# 4th_4G_-_V4_1.net
KiCad netlist of a schematic drawn in Altium Designer
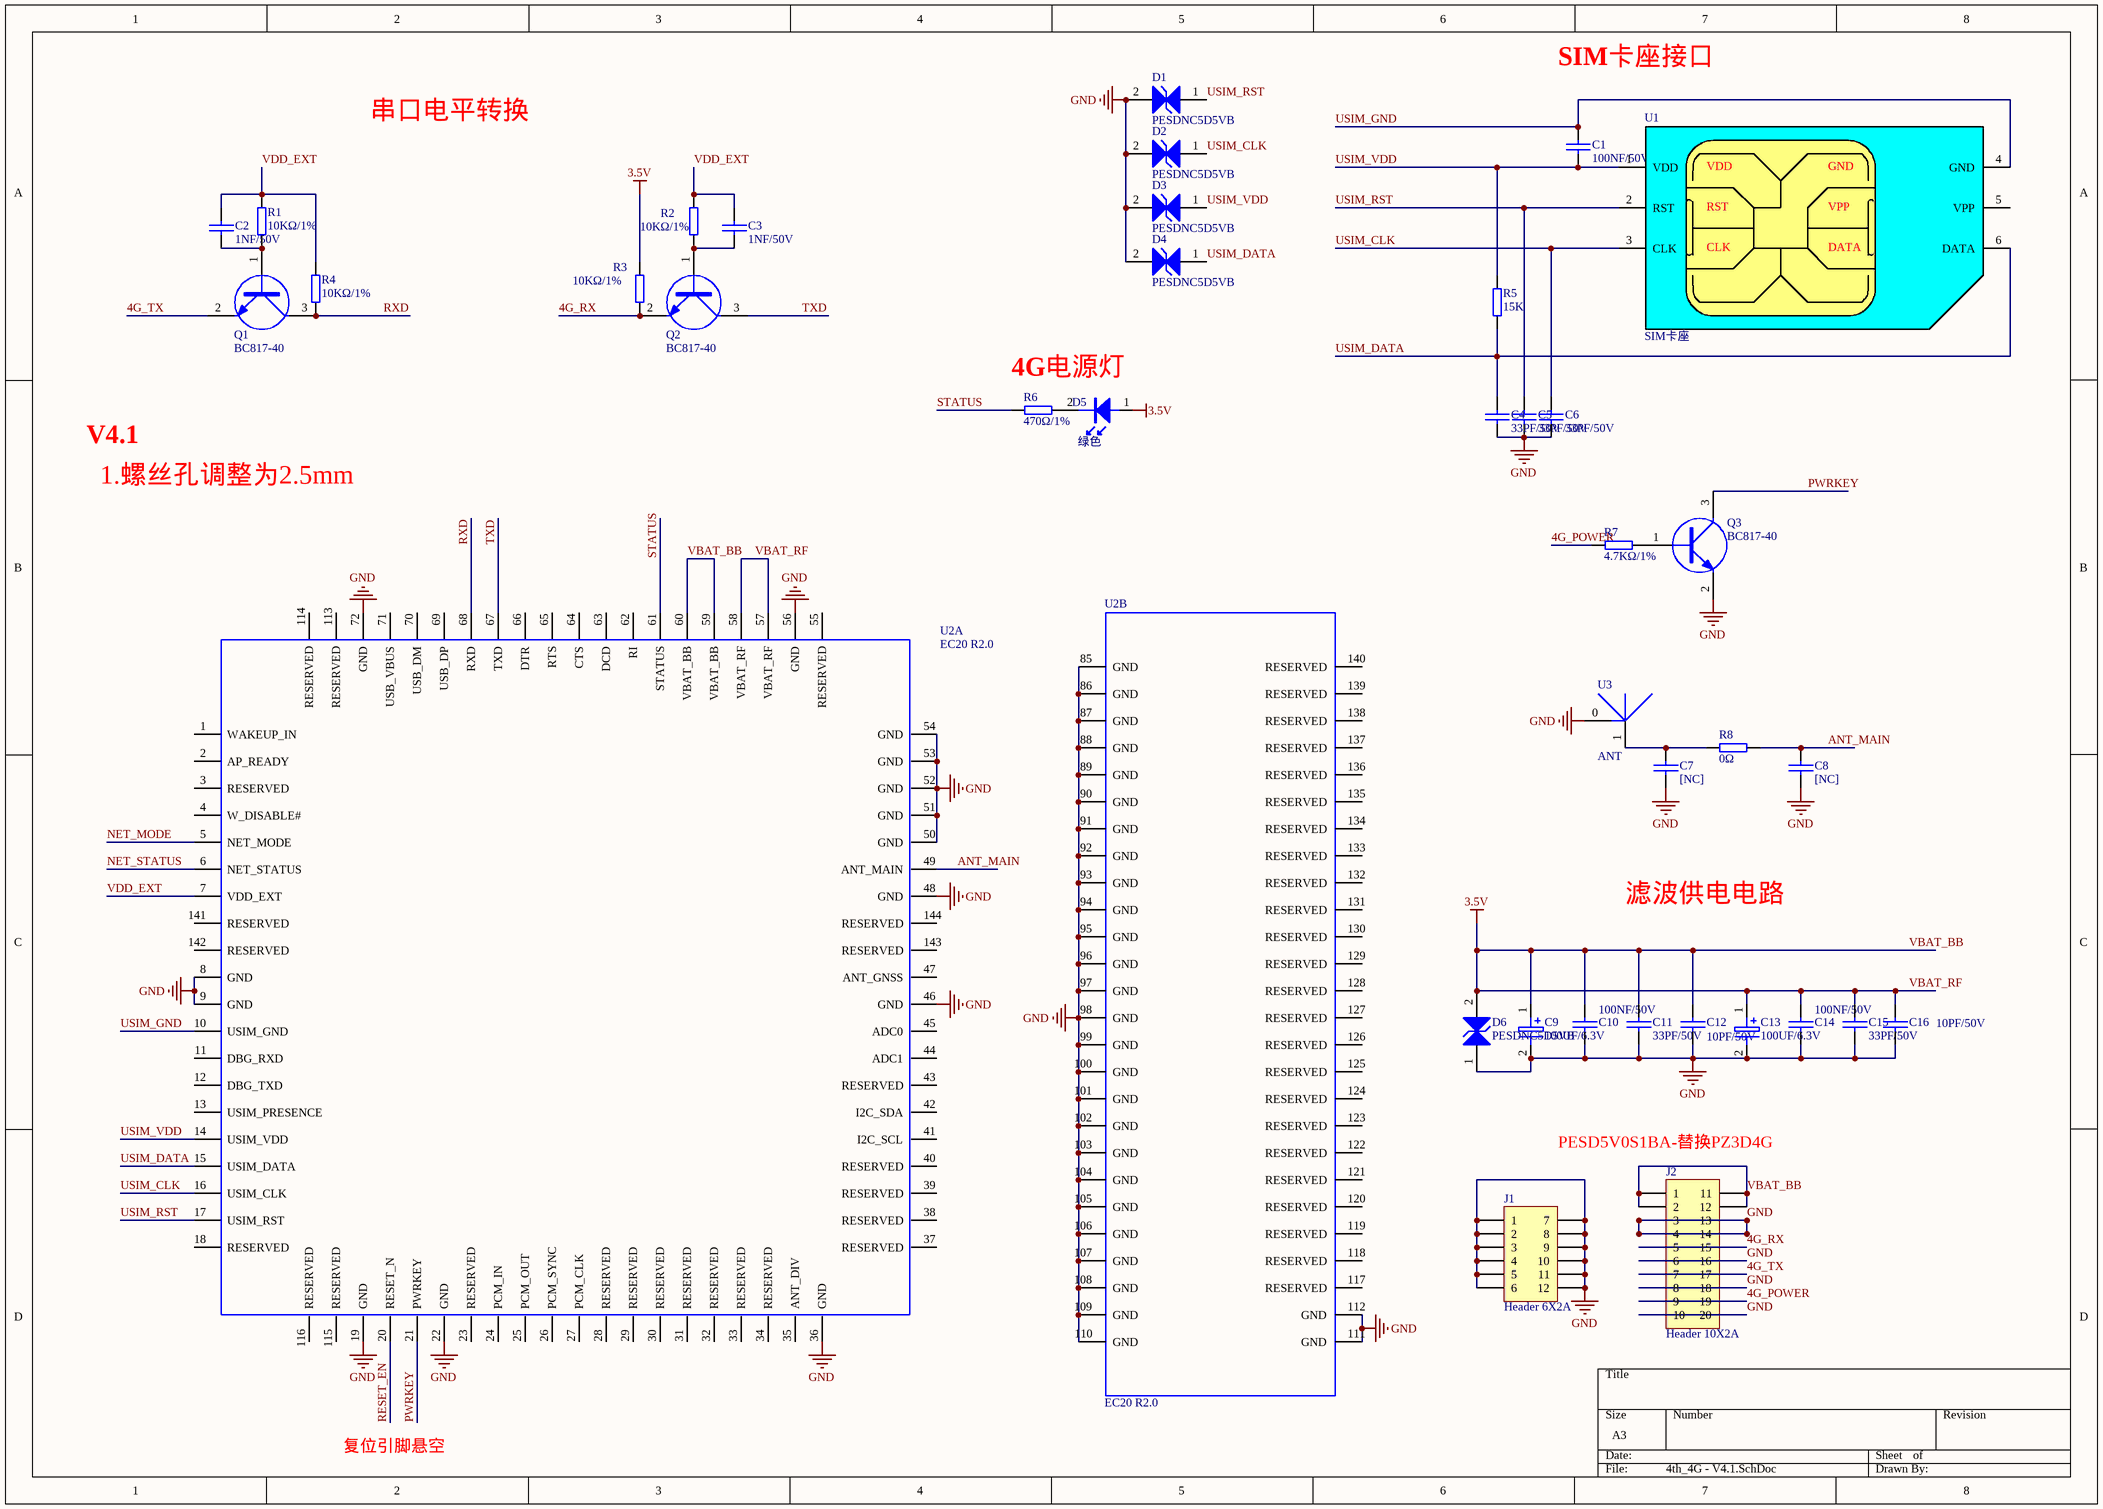
[diagram p0: 4th_4G - V4.1.SchDoc]

(export (version "E")
  (design (tool "Eeschema 10.0.6"))
  (components
    (comp (ref "C1")
      (value "100NF/50V")
      (footprint "0603_C")
      (description "无极性电容")
      (libsource (lib "Integrated_Library") (part "CAP"))
    )
    (comp (ref "C2")
      (value "1NF/50V")
      (footprint "0603_C")
      (description "无极性电容")
      (libsource (lib "Integrated_Library") (part "CAP"))
    )
    (comp (ref "C3")
      (value "1NF/50V")
      (footprint "0603_C")
      (description "无极性电容")
      (libsource (lib "Integrated_Library") (part "CAP"))
    )
    (comp (ref "C4")
      (value "33PF/50V")
      (footprint "0603_C")
      (description "无极性电容")
      (libsource (lib "Integrated_Library") (part "CAP"))
    )
    (comp (ref "C5")
      (value "33PF/50V")
      (footprint "0603_C")
      (description "无极性电容")
      (libsource (lib "Integrated_Library") (part "CAP"))
    )
    (comp (ref "C6")
      (value "33PF/50V")
      (footprint "0603_C")
      (description "无极性电容")
      (libsource (lib "Integrated_Library") (part "CAP"))
    )
    (comp (ref "C7")
      (value "[NC]")
      (footprint "0603_C")
      (description "无极性电容")
      (libsource (lib "Integrated_Library") (part "CAP"))
    )
    (comp (ref "C8")
      (value "[NC]")
      (footprint "0603_C")
      (description "无极性电容")
      (libsource (lib "Integrated_Library") (part "CAP"))
    )
    (comp (ref "C9")
      (value "100UF/6.3V")
      (footprint "CASE-B_3528")
      (description "钽电容")
      (libsource (lib "Integrated_Library") (part "CAP POLAR"))
    )
    (comp (ref "C10")
      (value "100NF/50V")
      (footprint "0603_C")
      (description "无极性电容")
      (libsource (lib "Integrated_Library") (part "CAP"))
    )
    (comp (ref "C11")
      (value "33PF/50V")
      (footprint "0603_C")
      (description "无极性电容")
      (libsource (lib "Integrated_Library") (part "CAP"))
    )
    (comp (ref "C12")
      (value "10PF/50V")
      (footprint "0603_C")
      (description "无极性电容")
      (libsource (lib "Integrated_Library") (part "CAP"))
    )
    (comp (ref "C13")
      (value "100UF/6.3V")
      (footprint "CASE-B_3528")
      (description "钽电容")
      (libsource (lib "Integrated_Library") (part "CAP POLAR"))
    )
    (comp (ref "C14")
      (value "100NF/50V")
      (footprint "0603_C")
      (description "无极性电容")
      (libsource (lib "Integrated_Library") (part "CAP"))
    )
    (comp (ref "C15")
      (value "33PF/50V")
      (footprint "0603_C")
      (description "无极性电容")
      (libsource (lib "Integrated_Library") (part "CAP"))
    )
    (comp (ref "C16")
      (value "10PF/50V")
      (footprint "0603_C")
      (description "无极性电容")
      (libsource (lib "Integrated_Library") (part "CAP"))
    )
    (comp (ref "D1")
      (value "PESDNC5D5VB")
      (footprint "SOD-523")
      (description "TVS 瞬态抑制二极管")
      (fields (field (name "PUBLISHER") "Altium Limited"))
      (libsource (lib "Integrated_Library") (part "TVS"))
    )
    (comp (ref "D2")
      (value "PESDNC5D5VB")
      (footprint "SOD-523")
      (description "TVS 瞬态抑制二极管")
      (fields (field (name "PUBLISHER") "Altium Limited"))
      (libsource (lib "Integrated_Library") (part "TVS"))
    )
    (comp (ref "D3")
      (value "PESDNC5D5VB")
      (footprint "SOD-523")
      (description "TVS 瞬态抑制二极管")
      (fields (field (name "PUBLISHER") "Altium Limited"))
      (libsource (lib "Integrated_Library") (part "TVS"))
    )
    (comp (ref "D4")
      (value "PESDNC5D5VB")
      (footprint "SOD-523")
      (description "TVS 瞬态抑制二极管")
      (fields (field (name "PUBLISHER") "Altium Limited"))
      (libsource (lib "Integrated_Library") (part "TVS"))
    )
    (comp (ref "D5")
      (value "绿色")
      (footprint "0603_D")
      (description "发光二极管")
      (libsource (lib "Integrated_Library") (part "LED"))
    )
    (comp (ref "D6")
      (value "PESDNC5D5VB")
      (footprint "SOD-523")
      (description "TVS 瞬态抑制二极管")
      (fields (field (name "PUBLISHER") "Altium Limited"))
      (libsource (lib "Integrated_Library") (part "TVS"))
    )
    (comp (ref "J1")
      (value "Header 6X2A")
      (footprint "HDR2X6_CEN")
      (description "Header, 6-Pin, Dual row")
      (fields (field (name "PUBLISHER") "Altium Limited"))
      (libsource (lib "Miscellaneous Connectors") (part "Header 6X2A"))
    )
    (comp (ref "J2")
      (value "Header 10X2A")
      (footprint "HDR2X10_CEN")
      (description "Header, 10-Pin, Dual row")
      (fields (field (name "PUBLISHER") "Altium Limited"))
      (libsource (lib "Miscellaneous Connectors") (part "Header 10X2A"))
    )
    (comp (ref "Q1")
      (value "BC817-40")
      (footprint "SOT-23-3")
      (description "NPN")
      (libsource (lib "Integrated_Library") (part "S8050"))
    )
    (comp (ref "Q2")
      (value "BC817-40")
      (footprint "SOT-23-3")
      (description "NPN")
      (libsource (lib "Integrated_Library") (part "S8050"))
    )
    (comp (ref "Q3")
      (value "BC817-40")
      (footprint "SOT-23-3")
      (description "NPN三极管")
      (libsource (lib "Integrated_Library") (part "BC817-40"))
    )
    (comp (ref "R1")
      (value "10KΩ/1%")
      (footprint "0603_R")
      (description "电阻")
      (libsource (lib "Integrated_Library") (part "RES2"))
    )
    (comp (ref "R2")
      (value "10KΩ/1%")
      (footprint "0603_R")
      (description "电阻")
      (libsource (lib "Integrated_Library") (part "RES2"))
    )
    (comp (ref "R3")
      (value "10KΩ/1%")
      (footprint "0603_R")
      (description "电阻")
      (libsource (lib "Integrated_Library") (part "RES2"))
    )
    (comp (ref "R4")
      (value "10KΩ/1%")
      (footprint "0603_R")
      (description "电阻")
      (libsource (lib "Integrated_Library") (part "RES2"))
    )
    (comp (ref "R5")
      (value "15K")
      (footprint "0603_R")
      (description "电阻")
      (libsource (lib "Integrated_Library") (part "RES2"))
    )
    (comp (ref "R6")
      (value "470Ω/1%")
      (footprint "0603_R")
      (description "电阻")
      (libsource (lib "Integrated_Library") (part "RES2"))
    )
    (comp (ref "R7")
      (value "4.7KΩ/1%")
      (footprint "0603_R")
      (description "电阻")
      (libsource (lib "Integrated_Library") (part "RES2"))
    )
    (comp (ref "R8")
      (value "0Ω")
      (footprint "0603_R")
      (description "电阻")
      (libsource (lib "Integrated_Library") (part "RES2"))
    )
    (comp (ref "U1")
      (value "SIM卡座")
      (footprint "SIM卡座-NANO掀盖式")
      (description "无保护引脚SIM卡座")
      (libsource (lib "MyLib Schlib") (part "SIM卡座"))
    )
    (comp (ref "U2")
      (value "EC20 R2.0")
      (footprint "EC20_R2.0")
      (description "移远通信4G")
      (libsource (lib "Integrated_Library") (part "EC20 R2.0"))
    )
    (comp (ref "U3")
      (value "ANT")
      (footprint "SMA-KWE/弯头")
      (description "天线座")
      (libsource (lib "Integrated_Library") (part "ANT"))
    )
  )
  (nets
    (net (code "1") (name "/4G_POWER") (class "Default")
      (node (ref "J2") (pin "19") (pinfunction "19_19") (pintype "passive"))
      (node (ref "J2") (pin "9") (pinfunction "9_9") (pintype "passive"))
      (node (ref "R7") (pin "1") (pinfunction "1_1") (pintype "passive"))
    )
    (net (code "2") (name "/4G_RX") (class "Default")
      (node (ref "J2") (pin "15") (pinfunction "15_15") (pintype "passive"))
      (node (ref "J2") (pin "5") (pinfunction "5_5") (pintype "passive"))
      (node (ref "Q2") (pin "2") (pinfunction "2_2") (pintype "passive"))
      (node (ref "R3") (pin "1") (pinfunction "1_1") (pintype "passive"))
    )
    (net (code "3") (name "/4G_TX") (class "Default")
      (node (ref "J2") (pin "17") (pinfunction "17_17") (pintype "passive"))
      (node (ref "J2") (pin "7") (pinfunction "7_7") (pintype "passive"))
      (node (ref "Q1") (pin "2") (pinfunction "2_2") (pintype "passive"))
    )
    (net (code "4") (name "/ANT_MAIN") (class "Default")
      (node (ref "C8") (pin "1") (pinfunction "1_1") (pintype "passive"))
      (node (ref "R8") (pin "2") (pinfunction "2_2") (pintype "passive"))
      (node (ref "U2") (pin "49") (pinfunction "ANT_MAIN_49") (pintype "passive"))
    )
    (net (code "5") (name "/NET_MODE") (class "Default")
      (node (ref "U2") (pin "5") (pinfunction "NET_MODE_5") (pintype "passive"))
    )
    (net (code "6") (name "/NET_STATUS") (class "Default")
      (node (ref "U2") (pin "6") (pinfunction "NET_STATUS_6") (pintype "passive"))
    )
    (net (code "7") (name "/PWRKEY") (class "Default")
      (node (ref "Q3") (pin "3") (pinfunction "3_3") (pintype "passive"))
      (node (ref "U2") (pin "21") (pinfunction "PWRKEY_21") (pintype "passive"))
    )
    (net (code "8") (name "/RESET_EN") (class "Default")
      (node (ref "U2") (pin "20") (pinfunction "RESET_N_20") (pintype "passive"))
    )
    (net (code "9") (name "/RXD") (class "Default")
      (node (ref "Q1") (pin "3") (pinfunction "3_3") (pintype "passive"))
      (node (ref "R4") (pin "1") (pinfunction "1_1") (pintype "passive"))
      (node (ref "U2") (pin "68") (pinfunction "RXD_68") (pintype "passive"))
    )
    (net (code "10") (name "/STATUS") (class "Default")
      (node (ref "R6") (pin "1") (pinfunction "1_1") (pintype "passive"))
      (node (ref "U2") (pin "61") (pinfunction "STATUS_61") (pintype "passive"))
    )
    (net (code "11") (name "/TXD") (class "Default")
      (node (ref "Q2") (pin "3") (pinfunction "3_3") (pintype "passive"))
      (node (ref "U2") (pin "67") (pinfunction "TXD_67") (pintype "passive"))
    )
    (net (code "12") (name "/USIM_CLK") (class "Default")
      (node (ref "C6") (pin "1") (pinfunction "1_1") (pintype "passive"))
      (node (ref "D2") (pin "1") (pinfunction "1_1") (pintype "passive"))
      (node (ref "U1") (pin "3") (pinfunction "CLK_3") (pintype "passive"))
      (node (ref "U2") (pin "16") (pinfunction "USIM_CLK_16") (pintype "passive"))
    )
    (net (code "13") (name "/USIM_DATA") (class "Default")
      (node (ref "C4") (pin "1") (pinfunction "1_1") (pintype "passive"))
      (node (ref "D4") (pin "1") (pinfunction "1_1") (pintype "passive"))
      (node (ref "R5") (pin "1") (pinfunction "1_1") (pintype "passive"))
      (node (ref "U1") (pin "6") (pinfunction "DATA_6") (pintype "passive"))
      (node (ref "U2") (pin "15") (pinfunction "USIM_DATA_15") (pintype "passive"))
    )
    (net (code "14") (name "/USIM_GND") (class "Default")
      (node (ref "C1") (pin "1") (pinfunction "1_1") (pintype "passive"))
      (node (ref "U1") (pin "4") (pinfunction "GND_4") (pintype "passive"))
      (node (ref "U2") (pin "10") (pinfunction "USIM_GND_10") (pintype "passive"))
    )
    (net (code "15") (name "/USIM_RST") (class "Default")
      (node (ref "C5") (pin "1") (pinfunction "1_1") (pintype "passive"))
      (node (ref "D1") (pin "1") (pinfunction "1_1") (pintype "passive"))
      (node (ref "U1") (pin "2") (pinfunction "RST_2") (pintype "passive"))
      (node (ref "U2") (pin "17") (pinfunction "USIM_RST_17") (pintype "passive"))
    )
    (net (code "16") (name "/USIM_VDD") (class "Default")
      (node (ref "C1") (pin "2") (pinfunction "2_2") (pintype "passive"))
      (node (ref "D3") (pin "1") (pinfunction "1_1") (pintype "passive"))
      (node (ref "R5") (pin "2") (pinfunction "2_2") (pintype "passive"))
      (node (ref "U1") (pin "1") (pinfunction "VDD_1") (pintype "passive"))
      (node (ref "U2") (pin "14") (pinfunction "USIM_VDD_14") (pintype "passive"))
    )
    (net (code "17") (name "/VDD_EXT") (class "Default")
      (node (ref "C2") (pin "1") (pinfunction "1_1") (pintype "passive"))
      (node (ref "C3") (pin "1") (pinfunction "1_1") (pintype "passive"))
      (node (ref "R1") (pin "2") (pinfunction "2_2") (pintype "passive"))
      (node (ref "R2") (pin "2") (pinfunction "2_2") (pintype "passive"))
      (node (ref "R4") (pin "2") (pinfunction "2_2") (pintype "passive"))
      (node (ref "U2") (pin "7") (pinfunction "VDD_EXT_7") (pintype "passive"))
    )
    (net (code "18") (name "3.5V") (class "Default")
      (node (ref "C10") (pin "1") (pinfunction "1_1") (pintype "passive"))
      (node (ref "C11") (pin "1") (pinfunction "1_1") (pintype "passive"))
      (node (ref "C12") (pin "1") (pinfunction "1_1") (pintype "passive"))
      (node (ref "C13") (pin "1") (pinfunction "1_1") (pintype "passive"))
      (node (ref "C14") (pin "1") (pinfunction "1_1") (pintype "passive"))
      (node (ref "C15") (pin "1") (pinfunction "1_1") (pintype "passive"))
      (node (ref "C16") (pin "1") (pinfunction "1_1") (pintype "passive"))
      (node (ref "C9") (pin "1") (pinfunction "1_1") (pintype "passive"))
      (node (ref "D5") (pin "1") (pinfunction "1_1") (pintype "passive"))
      (node (ref "D6") (pin "2") (pinfunction "K_2") (pintype "passive"))
      (node (ref "J2") (pin "1") (pinfunction "1_1") (pintype "passive"))
      (node (ref "J2") (pin "11") (pinfunction "11_11") (pintype "passive"))
      (node (ref "J2") (pin "12") (pinfunction "12_12") (pintype "passive"))
      (node (ref "J2") (pin "2") (pinfunction "2_2") (pintype "passive"))
      (node (ref "R3") (pin "2") (pinfunction "2_2") (pintype "passive"))
      (node (ref "U2") (pin "57") (pinfunction "VBAT_RF_57") (pintype "passive"))
      (node (ref "U2") (pin "58") (pinfunction "VBAT_RF_58") (pintype "passive"))
      (node (ref "U2") (pin "59") (pinfunction "VBAT_BB_59") (pintype "passive"))
      (node (ref "U2") (pin "60") (pinfunction "VBAT_BB_60") (pintype "passive"))
    )
    (net (code "19") (name "GND") (class "Default")
      (node (ref "C10") (pin "2") (pinfunction "2_2") (pintype "passive"))
      (node (ref "C11") (pin "2") (pinfunction "2_2") (pintype "passive"))
      (node (ref "C12") (pin "2") (pinfunction "2_2") (pintype "passive"))
      (node (ref "C13") (pin "2") (pinfunction "2_2") (pintype "passive"))
      (node (ref "C14") (pin "2") (pinfunction "2_2") (pintype "passive"))
      (node (ref "C15") (pin "2") (pinfunction "2_2") (pintype "passive"))
      (node (ref "C16") (pin "2") (pinfunction "2_2") (pintype "passive"))
      (node (ref "C4") (pin "2") (pinfunction "2_2") (pintype "passive"))
      (node (ref "C5") (pin "2") (pinfunction "2_2") (pintype "passive"))
      (node (ref "C6") (pin "2") (pinfunction "2_2") (pintype "passive"))
      (node (ref "C7") (pin "2") (pinfunction "2_2") (pintype "passive"))
      (node (ref "C8") (pin "2") (pinfunction "2_2") (pintype "passive"))
      (node (ref "C9") (pin "2") (pinfunction "2_2") (pintype "passive"))
      (node (ref "D1") (pin "2") (pinfunction "K_2") (pintype "passive"))
      (node (ref "D2") (pin "2") (pinfunction "K_2") (pintype "passive"))
      (node (ref "D3") (pin "2") (pinfunction "K_2") (pintype "passive"))
      (node (ref "D4") (pin "2") (pinfunction "K_2") (pintype "passive"))
      (node (ref "D6") (pin "1") (pinfunction "1_1") (pintype "passive"))
      (node (ref "J1") (pin "1") (pinfunction "1_1") (pintype "passive"))
      (node (ref "J1") (pin "10") (pinfunction "10_10") (pintype "passive"))
      (node (ref "J1") (pin "11") (pinfunction "11_11") (pintype "passive"))
      (node (ref "J1") (pin "12") (pinfunction "12_12") (pintype "passive"))
      (node (ref "J1") (pin "2") (pinfunction "2_2") (pintype "passive"))
      (node (ref "J1") (pin "3") (pinfunction "3_3") (pintype "passive"))
      (node (ref "J1") (pin "4") (pinfunction "4_4") (pintype "passive"))
      (node (ref "J1") (pin "5") (pinfunction "5_5") (pintype "passive"))
      (node (ref "J1") (pin "6") (pinfunction "6_6") (pintype "passive"))
      (node (ref "J1") (pin "7") (pinfunction "7_7") (pintype "passive"))
      (node (ref "J1") (pin "8") (pinfunction "8_8") (pintype "passive"))
      (node (ref "J1") (pin "9") (pinfunction "9_9") (pintype "passive"))
      (node (ref "J2") (pin "10") (pinfunction "10_10") (pintype "passive"))
      (node (ref "J2") (pin "13") (pinfunction "13_13") (pintype "passive"))
      (node (ref "J2") (pin "14") (pinfunction "14_14") (pintype "passive"))
      (node (ref "J2") (pin "16") (pinfunction "16_16") (pintype "passive"))
      (node (ref "J2") (pin "18") (pinfunction "18_18") (pintype "passive"))
      (node (ref "J2") (pin "20") (pinfunction "20_20") (pintype "passive"))
      (node (ref "J2") (pin "3") (pinfunction "3_3") (pintype "passive"))
      (node (ref "J2") (pin "4") (pinfunction "4_4") (pintype "passive"))
      (node (ref "J2") (pin "6") (pinfunction "6_6") (pintype "passive"))
      (node (ref "J2") (pin "8") (pinfunction "8_8") (pintype "passive"))
      (node (ref "Q3") (pin "2") (pinfunction "2_2") (pintype "passive"))
      (node (ref "U2") (pin "100") (pinfunction "GND_100") (pintype "passive"))
      (node (ref "U2") (pin "101") (pinfunction "GND_101") (pintype "passive"))
      (node (ref "U2") (pin "102") (pinfunction "GND_102") (pintype "passive"))
      (node (ref "U2") (pin "103") (pinfunction "GND_103") (pintype "passive"))
      (node (ref "U2") (pin "104") (pinfunction "GND_104") (pintype "passive"))
      (node (ref "U2") (pin "105") (pinfunction "GND_105") (pintype "passive"))
      (node (ref "U2") (pin "106") (pinfunction "GND_106") (pintype "passive"))
      (node (ref "U2") (pin "107") (pinfunction "GND_107") (pintype "passive"))
      (node (ref "U2") (pin "108") (pinfunction "GND_108") (pintype "passive"))
      (node (ref "U2") (pin "109") (pinfunction "GND_109") (pintype "passive"))
      (node (ref "U2") (pin "110") (pinfunction "GND_110") (pintype "passive"))
      (node (ref "U2") (pin "111") (pinfunction "GND_111") (pintype "passive"))
      (node (ref "U2") (pin "112") (pinfunction "GND_112") (pintype "passive"))
      (node (ref "U2") (pin "19") (pinfunction "GND_19") (pintype "passive"))
      (node (ref "U2") (pin "22") (pinfunction "GND_22") (pintype "passive"))
      (node (ref "U2") (pin "36") (pinfunction "GND_36") (pintype "passive"))
      (node (ref "U2") (pin "46") (pinfunction "GND_46") (pintype "passive"))
      (node (ref "U2") (pin "48") (pinfunction "GND_48") (pintype "passive"))
      (node (ref "U2") (pin "50") (pinfunction "GND_50") (pintype "passive"))
      (node (ref "U2") (pin "51") (pinfunction "GND_51") (pintype "passive"))
      (node (ref "U2") (pin "52") (pinfunction "GND_52") (pintype "passive"))
      (node (ref "U2") (pin "53") (pinfunction "GND_53") (pintype "passive"))
      (node (ref "U2") (pin "54") (pinfunction "GND_54") (pintype "passive"))
      (node (ref "U2") (pin "56") (pinfunction "GND_56") (pintype "passive"))
      (node (ref "U2") (pin "72") (pinfunction "GND_72") (pintype "passive"))
      (node (ref "U2") (pin "8") (pinfunction "GND_8") (pintype "passive"))
      (node (ref "U2") (pin "85") (pinfunction "GND_85") (pintype "passive"))
      (node (ref "U2") (pin "86") (pinfunction "GND_86") (pintype "passive"))
      (node (ref "U2") (pin "87") (pinfunction "GND_87") (pintype "passive"))
      (node (ref "U2") (pin "88") (pinfunction "GND_88") (pintype "passive"))
      (node (ref "U2") (pin "89") (pinfunction "GND_89") (pintype "passive"))
      (node (ref "U2") (pin "9") (pinfunction "GND_9") (pintype "passive"))
      (node (ref "U2") (pin "90") (pinfunction "GND_90") (pintype "passive"))
      (node (ref "U2") (pin "91") (pinfunction "GND_91") (pintype "passive"))
      (node (ref "U2") (pin "92") (pinfunction "GND_92") (pintype "passive"))
      (node (ref "U2") (pin "93") (pinfunction "GND_93") (pintype "passive"))
      (node (ref "U2") (pin "94") (pinfunction "GND_94") (pintype "passive"))
      (node (ref "U2") (pin "95") (pinfunction "GND_95") (pintype "passive"))
      (node (ref "U2") (pin "96") (pinfunction "GND_96") (pintype "passive"))
      (node (ref "U2") (pin "97") (pinfunction "GND_97") (pintype "passive"))
      (node (ref "U2") (pin "98") (pinfunction "GND_98") (pintype "passive"))
      (node (ref "U2") (pin "99") (pinfunction "GND_99") (pintype "passive"))
      (node (ref "U3") (pin "0") (pinfunction "0_0") (pintype "passive"))
    )
    (net (code "20") (name "Net-(C2-Pad2)") (class "Default")
      (node (ref "C2") (pin "2") (pinfunction "2_2") (pintype "passive"))
      (node (ref "Q1") (pin "1") (pinfunction "1_1") (pintype "passive"))
      (node (ref "R1") (pin "1") (pinfunction "1_1") (pintype "passive"))
    )
    (net (code "21") (name "Net-(C3-Pad2)") (class "Default")
      (node (ref "C3") (pin "2") (pinfunction "2_2") (pintype "passive"))
      (node (ref "Q2") (pin "1") (pinfunction "1_1") (pintype "passive"))
      (node (ref "R2") (pin "1") (pinfunction "1_1") (pintype "passive"))
    )
    (net (code "22") (name "Net-(C7-Pad1)") (class "Default")
      (node (ref "C7") (pin "1") (pinfunction "1_1") (pintype "passive"))
      (node (ref "R8") (pin "1") (pinfunction "1_1") (pintype "passive"))
      (node (ref "U3") (pin "1") (pinfunction "1_1") (pintype "passive"))
    )
    (net (code "23") (name "Net-(D5-Pad2)") (class "Default")
      (node (ref "D5") (pin "2") (pinfunction "2_2") (pintype "passive"))
      (node (ref "R6") (pin "2") (pinfunction "2_2") (pintype "passive"))
    )
    (net (code "24") (name "Net-(Q3-Pad1)") (class "Default")
      (node (ref "Q3") (pin "1") (pinfunction "1_1") (pintype "passive"))
      (node (ref "R7") (pin "2") (pinfunction "2_2") (pintype "passive"))
    )
    (net (code "25") (name "unconnected-(U1-VPP-Pad5)") (class "Default")
      (node (ref "U1") (pin "5") (pinfunction "VPP_5") (pintype "passive"))
    )
    (net (code "26") (name "unconnected-(U2A-ADC0-Pad45)") (class "Default")
      (node (ref "U2") (pin "45") (pinfunction "ADC0_45") (pintype "passive"))
    )
    (net (code "27") (name "unconnected-(U2A-ADC1-Pad44)") (class "Default")
      (node (ref "U2") (pin "44") (pinfunction "ADC1_44") (pintype "passive"))
    )
    (net (code "28") (name "unconnected-(U2A-ANT_DIV-Pad35)") (class "Default")
      (node (ref "U2") (pin "35") (pinfunction "ANT_DIV_35") (pintype "passive"))
    )
    (net (code "29") (name "unconnected-(U2A-ANT_GNSS-Pad47)") (class "Default")
      (node (ref "U2") (pin "47") (pinfunction "ANT_GNSS_47") (pintype "passive"))
    )
    (net (code "30") (name "unconnected-(U2A-AP_READY-Pad2)") (class "Default")
      (node (ref "U2") (pin "2") (pinfunction "AP_READY_2") (pintype "passive"))
    )
    (net (code "31") (name "unconnected-(U2A-CTS-Pad64)") (class "Default")
      (node (ref "U2") (pin "64") (pinfunction "CTS_64") (pintype "passive"))
    )
    (net (code "32") (name "unconnected-(U2A-DBG_RXD-Pad11)") (class "Default")
      (node (ref "U2") (pin "11") (pinfunction "DBG_RXD_11") (pintype "passive"))
    )
    (net (code "33") (name "unconnected-(U2A-DBG_TXD-Pad12)") (class "Default")
      (node (ref "U2") (pin "12") (pinfunction "DBG_TXD_12") (pintype "passive"))
    )
    (net (code "34") (name "unconnected-(U2A-DCD-Pad63)") (class "Default")
      (node (ref "U2") (pin "63") (pinfunction "DCD_63") (pintype "passive"))
    )
    (net (code "35") (name "unconnected-(U2A-DTR-Pad66)") (class "Default")
      (node (ref "U2") (pin "66") (pinfunction "DTR_66") (pintype "passive"))
    )
    (net (code "36") (name "unconnected-(U2A-I2C_SCL-Pad41)") (class "Default")
      (node (ref "U2") (pin "41") (pinfunction "I2C_SCL_41") (pintype "passive"))
    )
    (net (code "37") (name "unconnected-(U2A-I2C_SDA-Pad42)") (class "Default")
      (node (ref "U2") (pin "42") (pinfunction "I2C_SDA_42") (pintype "passive"))
    )
    (net (code "38") (name "unconnected-(U2A-PCM_CLK-Pad27)") (class "Default")
      (node (ref "U2") (pin "27") (pinfunction "PCM_CLK_27") (pintype "passive"))
    )
    (net (code "39") (name "unconnected-(U2A-PCM_IN-Pad24)") (class "Default")
      (node (ref "U2") (pin "24") (pinfunction "PCM_IN_24") (pintype "passive"))
    )
    (net (code "40") (name "unconnected-(U2A-PCM_OUT-Pad25)") (class "Default")
      (node (ref "U2") (pin "25") (pinfunction "PCM_OUT_25") (pintype "passive"))
    )
    (net (code "41") (name "unconnected-(U2A-PCM_SYNC-Pad26)") (class "Default")
      (node (ref "U2") (pin "26") (pinfunction "PCM_SYNC_26") (pintype "passive"))
    )
    (net (code "42") (name "unconnected-(U2A-RESERVED-Pad3)") (class "Default")
      (node (ref "U2") (pin "3") (pinfunction "RESERVED_3") (pintype "passive"))
    )
    (net (code "43") (name "unconnected-(U2A-RESERVED-Pad18)") (class "Default")
      (node (ref "U2") (pin "18") (pinfunction "RESERVED_18") (pintype "passive"))
    )
    (net (code "44") (name "unconnected-(U2A-RESERVED-Pad23)") (class "Default")
      (node (ref "U2") (pin "23") (pinfunction "RESERVED_23") (pintype "passive"))
    )
    (net (code "45") (name "unconnected-(U2A-RESERVED-Pad28)") (class "Default")
      (node (ref "U2") (pin "28") (pinfunction "RESERVED_28") (pintype "passive"))
    )
    (net (code "46") (name "unconnected-(U2A-RESERVED-Pad29)") (class "Default")
      (node (ref "U2") (pin "29") (pinfunction "RESERVED_29") (pintype "passive"))
    )
    (net (code "47") (name "unconnected-(U2A-RESERVED-Pad30)") (class "Default")
      (node (ref "U2") (pin "30") (pinfunction "RESERVED_30") (pintype "passive"))
    )
    (net (code "48") (name "unconnected-(U2A-RESERVED-Pad31)") (class "Default")
      (node (ref "U2") (pin "31") (pinfunction "RESERVED_31") (pintype "passive"))
    )
    (net (code "49") (name "unconnected-(U2A-RESERVED-Pad32)") (class "Default")
      (node (ref "U2") (pin "32") (pinfunction "RESERVED_32") (pintype "passive"))
    )
    (net (code "50") (name "unconnected-(U2A-RESERVED-Pad33)") (class "Default")
      (node (ref "U2") (pin "33") (pinfunction "RESERVED_33") (pintype "passive"))
    )
    (net (code "51") (name "unconnected-(U2A-RESERVED-Pad34)") (class "Default")
      (node (ref "U2") (pin "34") (pinfunction "RESERVED_34") (pintype "passive"))
    )
    (net (code "52") (name "unconnected-(U2A-RESERVED-Pad37)") (class "Default")
      (node (ref "U2") (pin "37") (pinfunction "RESERVED_37") (pintype "passive"))
    )
    (net (code "53") (name "unconnected-(U2A-RESERVED-Pad38)") (class "Default")
      (node (ref "U2") (pin "38") (pinfunction "RESERVED_38") (pintype "passive"))
    )
    (net (code "54") (name "unconnected-(U2A-RESERVED-Pad39)") (class "Default")
      (node (ref "U2") (pin "39") (pinfunction "RESERVED_39") (pintype "passive"))
    )
    (net (code "55") (name "unconnected-(U2A-RESERVED-Pad40)") (class "Default")
      (node (ref "U2") (pin "40") (pinfunction "RESERVED_40") (pintype "passive"))
    )
    (net (code "56") (name "unconnected-(U2A-RESERVED-Pad43)") (class "Default")
      (node (ref "U2") (pin "43") (pinfunction "RESERVED_43") (pintype "passive"))
    )
    (net (code "57") (name "unconnected-(U2A-RESERVED-Pad55)") (class "Default")
      (node (ref "U2") (pin "55") (pinfunction "RESERVED_55") (pintype "passive"))
    )
    (net (code "58") (name "unconnected-(U2A-RESERVED-Pad113)") (class "Default")
      (node (ref "U2") (pin "113") (pinfunction "RESERVED_113") (pintype "passive"))
    )
    (net (code "59") (name "unconnected-(U2A-RESERVED-Pad114)") (class "Default")
      (node (ref "U2") (pin "114") (pinfunction "RESERVED_114") (pintype "passive"))
    )
    (net (code "60") (name "unconnected-(U2A-RESERVED-Pad115)") (class "Default")
      (node (ref "U2") (pin "115") (pinfunction "RESERVED_115") (pintype "passive"))
    )
    (net (code "61") (name "unconnected-(U2A-RESERVED-Pad116)") (class "Default")
      (node (ref "U2") (pin "116") (pinfunction "RESERVED_116") (pintype "passive"))
    )
    (net (code "62") (name "unconnected-(U2A-RESERVED-Pad141)") (class "Default")
      (node (ref "U2") (pin "141") (pinfunction "RESERVED_141") (pintype "passive"))
    )
    (net (code "63") (name "unconnected-(U2A-RESERVED-Pad142)") (class "Default")
      (node (ref "U2") (pin "142") (pinfunction "RESERVED_142") (pintype "passive"))
    )
    (net (code "64") (name "unconnected-(U2A-RESERVED-Pad143)") (class "Default")
      (node (ref "U2") (pin "143") (pinfunction "RESERVED_143") (pintype "passive"))
    )
    (net (code "65") (name "unconnected-(U2A-RESERVED-Pad144)") (class "Default")
      (node (ref "U2") (pin "144") (pinfunction "RESERVED_144") (pintype "passive"))
    )
    (net (code "66") (name "unconnected-(U2A-RI-Pad62)") (class "Default")
      (node (ref "U2") (pin "62") (pinfunction "RI_62") (pintype "passive"))
    )
    (net (code "67") (name "unconnected-(U2A-RTS-Pad65)") (class "Default")
      (node (ref "U2") (pin "65") (pinfunction "RTS_65") (pintype "passive"))
    )
    (net (code "68") (name "unconnected-(U2A-USB_DM-Pad70)") (class "Default")
      (node (ref "U2") (pin "70") (pinfunction "USB_DM_70") (pintype "passive"))
    )
    (net (code "69") (name "unconnected-(U2A-USB_DP-Pad69)") (class "Default")
      (node (ref "U2") (pin "69") (pinfunction "USB_DP_69") (pintype "passive"))
    )
    (net (code "70") (name "unconnected-(U2A-USB_VBUS-Pad71)") (class "Default")
      (node (ref "U2") (pin "71") (pinfunction "USB_VBUS_71") (pintype "passive"))
    )
    (net (code "71") (name "unconnected-(U2A-USIM_PRESENCE-Pad13)") (class "Default")
      (node (ref "U2") (pin "13") (pinfunction "USIM_PRESENCE_13") (pintype "passive"))
    )
    (net (code "72") (name "unconnected-(U2A-WAKEUP_IN-Pad1)") (class "Default")
      (node (ref "U2") (pin "1") (pinfunction "WAKEUP_IN_1") (pintype "passive"))
    )
    (net (code "73") (name "unconnected-(U2A-W_DISABLE#-Pad4)") (class "Default")
      (node (ref "U2") (pin "4") (pinfunction "W_DISABLE#_4") (pintype "passive"))
    )
    (net (code "74") (name "unconnected-(U2B-RESERVED-Pad117)") (class "Default")
      (node (ref "U2") (pin "117") (pinfunction "RESERVED_117") (pintype "passive"))
    )
    (net (code "75") (name "unconnected-(U2B-RESERVED-Pad118)") (class "Default")
      (node (ref "U2") (pin "118") (pinfunction "RESERVED_118") (pintype "passive"))
    )
    (net (code "76") (name "unconnected-(U2B-RESERVED-Pad119)") (class "Default")
      (node (ref "U2") (pin "119") (pinfunction "RESERVED_119") (pintype "passive"))
    )
    (net (code "77") (name "unconnected-(U2B-RESERVED-Pad120)") (class "Default")
      (node (ref "U2") (pin "120") (pinfunction "RESERVED_120") (pintype "passive"))
    )
    (net (code "78") (name "unconnected-(U2B-RESERVED-Pad121)") (class "Default")
      (node (ref "U2") (pin "121") (pinfunction "RESERVED_121") (pintype "passive"))
    )
    (net (code "79") (name "unconnected-(U2B-RESERVED-Pad122)") (class "Default")
      (node (ref "U2") (pin "122") (pinfunction "RESERVED_122") (pintype "passive"))
    )
    (net (code "80") (name "unconnected-(U2B-RESERVED-Pad123)") (class "Default")
      (node (ref "U2") (pin "123") (pinfunction "RESERVED_123") (pintype "passive"))
    )
    (net (code "81") (name "unconnected-(U2B-RESERVED-Pad124)") (class "Default")
      (node (ref "U2") (pin "124") (pinfunction "RESERVED_124") (pintype "passive"))
    )
    (net (code "82") (name "unconnected-(U2B-RESERVED-Pad125)") (class "Default")
      (node (ref "U2") (pin "125") (pinfunction "RESERVED_125") (pintype "passive"))
    )
    (net (code "83") (name "unconnected-(U2B-RESERVED-Pad126)") (class "Default")
      (node (ref "U2") (pin "126") (pinfunction "RESERVED_126") (pintype "passive"))
    )
    (net (code "84") (name "unconnected-(U2B-RESERVED-Pad127)") (class "Default")
      (node (ref "U2") (pin "127") (pinfunction "RESERVED_127") (pintype "passive"))
    )
    (net (code "85") (name "unconnected-(U2B-RESERVED-Pad128)") (class "Default")
      (node (ref "U2") (pin "128") (pinfunction "RESERVED_128") (pintype "passive"))
    )
    (net (code "86") (name "unconnected-(U2B-RESERVED-Pad129)") (class "Default")
      (node (ref "U2") (pin "129") (pinfunction "RESERVED_129") (pintype "passive"))
    )
    (net (code "87") (name "unconnected-(U2B-RESERVED-Pad130)") (class "Default")
      (node (ref "U2") (pin "130") (pinfunction "RESERVED_130") (pintype "passive"))
    )
    (net (code "88") (name "unconnected-(U2B-RESERVED-Pad131)") (class "Default")
      (node (ref "U2") (pin "131") (pinfunction "RESERVED_131") (pintype "passive"))
    )
    (net (code "89") (name "unconnected-(U2B-RESERVED-Pad132)") (class "Default")
      (node (ref "U2") (pin "132") (pinfunction "RESERVED_132") (pintype "passive"))
    )
    (net (code "90") (name "unconnected-(U2B-RESERVED-Pad133)") (class "Default")
      (node (ref "U2") (pin "133") (pinfunction "RESERVED_133") (pintype "passive"))
    )
    (net (code "91") (name "unconnected-(U2B-RESERVED-Pad134)") (class "Default")
      (node (ref "U2") (pin "134") (pinfunction "RESERVED_134") (pintype "passive"))
    )
    (net (code "92") (name "unconnected-(U2B-RESERVED-Pad135)") (class "Default")
      (node (ref "U2") (pin "135") (pinfunction "RESERVED_135") (pintype "passive"))
    )
    (net (code "93") (name "unconnected-(U2B-RESERVED-Pad136)") (class "Default")
      (node (ref "U2") (pin "136") (pinfunction "RESERVED_136") (pintype "passive"))
    )
    (net (code "94") (name "unconnected-(U2B-RESERVED-Pad137)") (class "Default")
      (node (ref "U2") (pin "137") (pinfunction "RESERVED_137") (pintype "passive"))
    )
    (net (code "95") (name "unconnected-(U2B-RESERVED-Pad138)") (class "Default")
      (node (ref "U2") (pin "138") (pinfunction "RESERVED_138") (pintype "passive"))
    )
    (net (code "96") (name "unconnected-(U2B-RESERVED-Pad139)") (class "Default")
      (node (ref "U2") (pin "139") (pinfunction "RESERVED_139") (pintype "passive"))
    )
    (net (code "97") (name "unconnected-(U2B-RESERVED-Pad140)") (class "Default")
      (node (ref "U2") (pin "140") (pinfunction "RESERVED_140") (pintype "passive"))
    )
  )
)
